# RGF_1_0.net
KiCad netlist of a schematic drawn in EAGLE
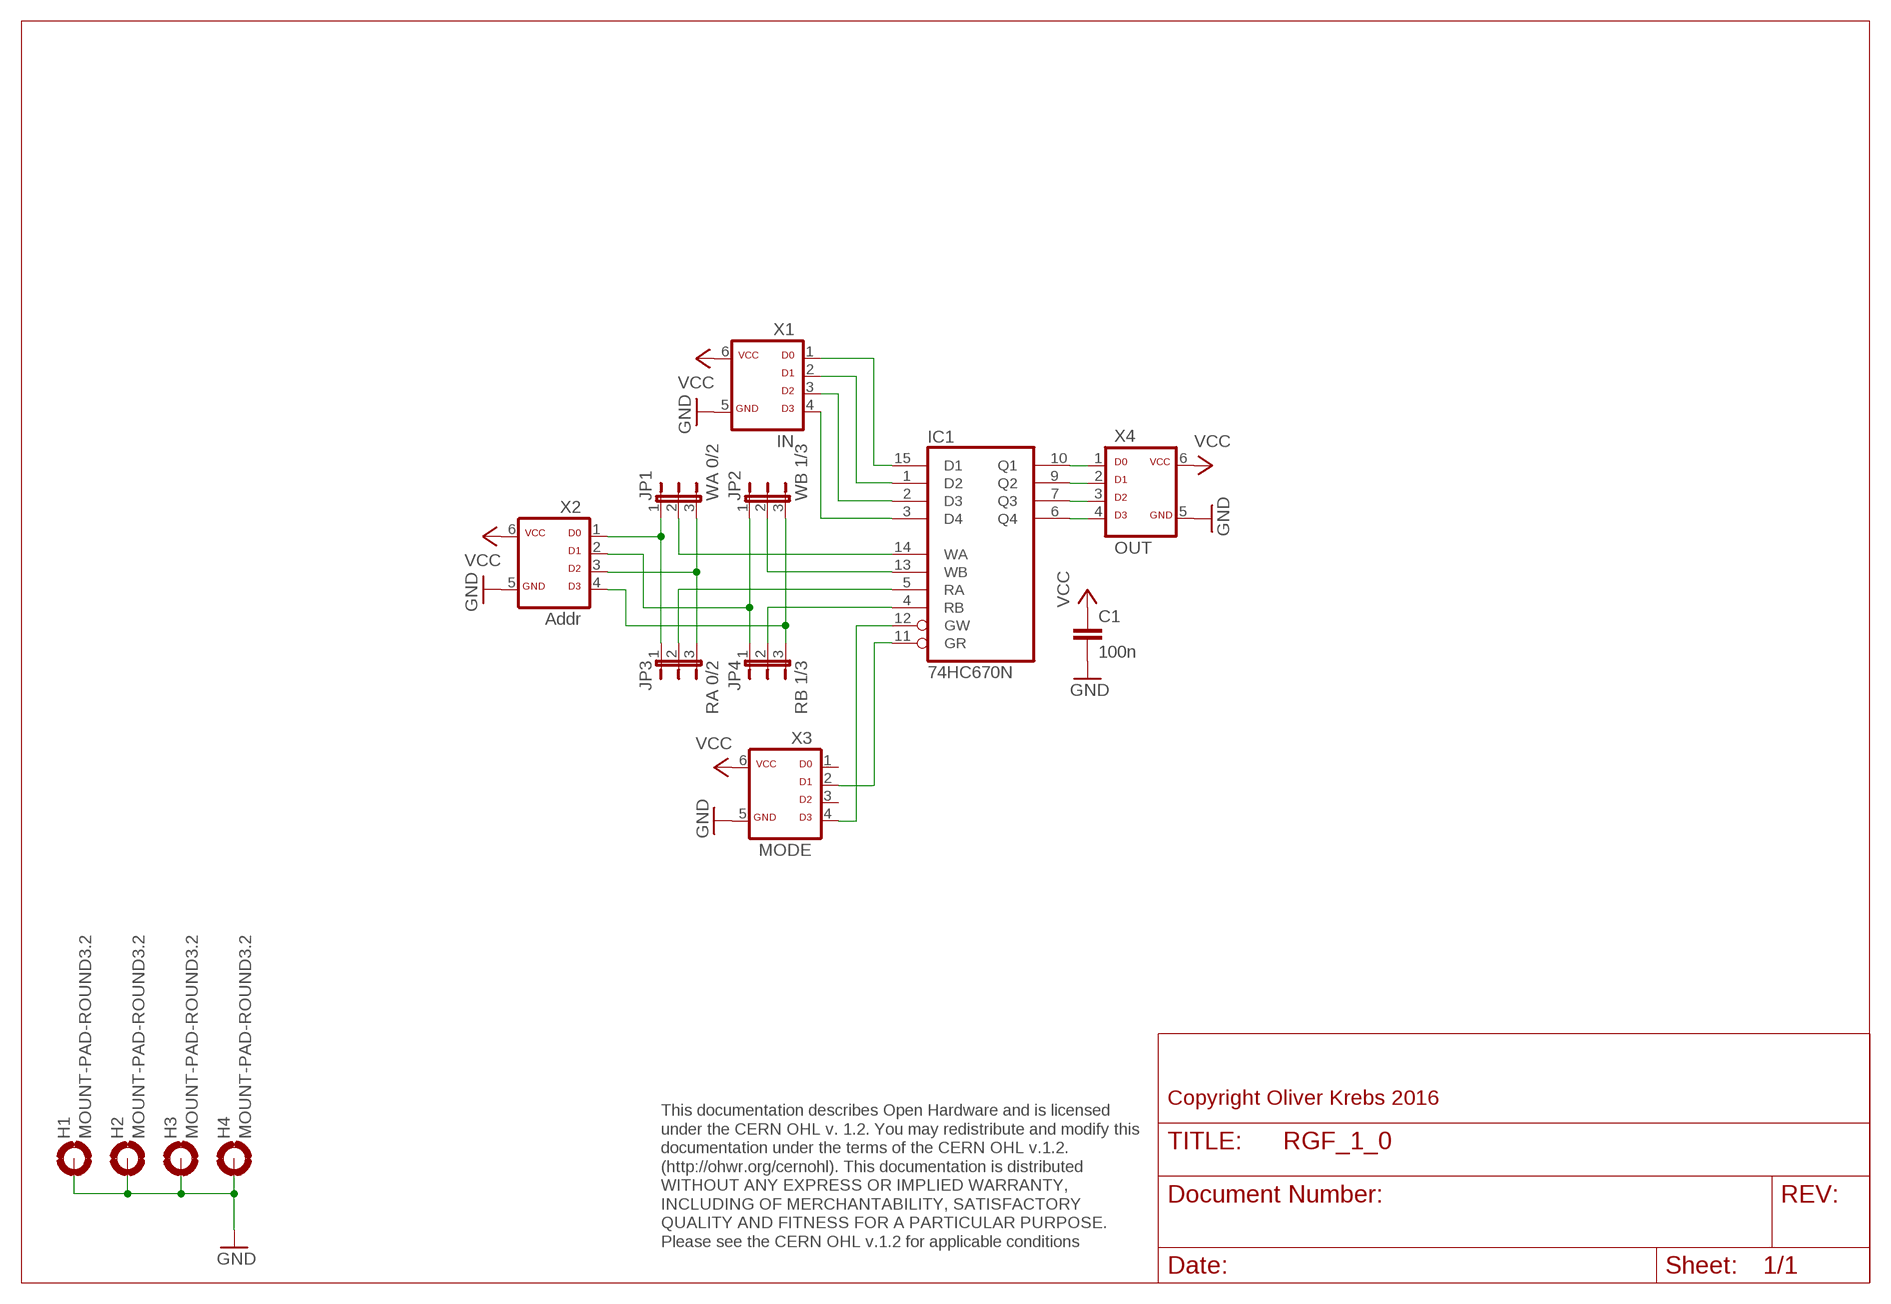
[diagram p0: schematic, sheet 1]

(export (version "E")
  (design (tool "Eeschema 10.0.6"))
  (components
    (comp (ref "C1")
      (value "100n")
      (footprint "eagle-import:C050-025X075")
      (libsource (lib "eagle-import") (part "C-EU050-025X075"))
    )
    (comp (ref "H1")
      (value "MOUNT-PAD-ROUND3.2")
      (footprint "eagle-import:3,2-PAD")
      (libsource (lib "eagle-import") (part "MOUNT-PAD-ROUND3.2"))
    )
    (comp (ref "H2")
      (value "MOUNT-PAD-ROUND3.2")
      (footprint "eagle-import:3,2-PAD")
      (libsource (lib "eagle-import") (part "MOUNT-PAD-ROUND3.2"))
    )
    (comp (ref "H3")
      (value "MOUNT-PAD-ROUND3.2")
      (footprint "eagle-import:3,2-PAD")
      (libsource (lib "eagle-import") (part "MOUNT-PAD-ROUND3.2"))
    )
    (comp (ref "H4")
      (value "MOUNT-PAD-ROUND3.2")
      (footprint "eagle-import:3,2-PAD")
      (libsource (lib "eagle-import") (part "MOUNT-PAD-ROUND3.2"))
    )
    (comp (ref "IC1")
      (value "74HC670N")
      (footprint "eagle-import:DIL16")
      (libsource (lib "eagle-import") (part "74670NHC"))
    )
    (comp (ref "JP1")
      (value "WA 0/2")
      (footprint "eagle-import:JP2")
      (libsource (lib "eagle-import") (part "JP2E"))
    )
    (comp (ref "JP2")
      (value "WB 1/3")
      (footprint "eagle-import:JP2")
      (libsource (lib "eagle-import") (part "JP2E"))
    )
    (comp (ref "JP3")
      (value "RA 0/2")
      (footprint "eagle-import:JP2")
      (libsource (lib "eagle-import") (part "JP2E"))
    )
    (comp (ref "JP4")
      (value "RB 1/3")
      (footprint "eagle-import:JP2")
      (libsource (lib "eagle-import") (part "JP2E"))
    )
    (comp (ref "X1")
      (value "IN")
      (footprint "eagle-import:ML-6")
      (libsource (lib "eagle-import") (part "ML6D"))
    )
    (comp (ref "X2")
      (value "Addr")
      (footprint "eagle-import:ML-6")
      (libsource (lib "eagle-import") (part "ML6D"))
    )
    (comp (ref "X3")
      (value "MODE")
      (footprint "eagle-import:ML-6")
      (libsource (lib "eagle-import") (part "ML6D"))
    )
    (comp (ref "X4")
      (value "OUT")
      (footprint "eagle-import:ML-6")
      (libsource (lib "eagle-import") (part "ML6D"))
    )
  )
  (nets
    (net (code "1") (name "GND") (class "Default")
      (node (ref "C1") (pin "2") (pinfunction "2_2") (pintype "passive"))
      (node (ref "H1") (pin "B3,2") (pinfunction "MOUNT_B3,2") (pintype "passive"))
      (node (ref "H2") (pin "B3,2") (pinfunction "MOUNT_B3,2") (pintype "passive"))
      (node (ref "H3") (pin "B3,2") (pinfunction "MOUNT_B3,2") (pintype "passive"))
      (node (ref "H4") (pin "B3,2") (pinfunction "MOUNT_B3,2") (pintype "passive"))
      (node (ref "X1") (pin "5") (pinfunction "5_5") (pintype "passive"))
      (node (ref "X2") (pin "5") (pinfunction "5_5") (pintype "passive"))
      (node (ref "X3") (pin "5") (pinfunction "5_5") (pintype "passive"))
      (node (ref "X4") (pin "5") (pinfunction "5_5") (pintype "passive"))
    )
    (net (code "2") (name "Net-(IC1A-D1)") (class "Default")
      (node (ref "IC1") (pin "15") (pinfunction "D1_15") (pintype "input"))
      (node (ref "X1") (pin "1") (pinfunction "1_1") (pintype "passive"))
    )
    (net (code "3") (name "Net-(IC1A-D2)") (class "Default")
      (node (ref "IC1") (pin "1") (pinfunction "D2_1") (pintype "input"))
      (node (ref "X1") (pin "2") (pinfunction "2_2") (pintype "passive"))
    )
    (net (code "4") (name "Net-(IC1A-D3)") (class "Default")
      (node (ref "IC1") (pin "2") (pinfunction "D3_2") (pintype "input"))
      (node (ref "X1") (pin "3") (pinfunction "3_3") (pintype "passive"))
    )
    (net (code "5") (name "Net-(IC1A-D4)") (class "Default")
      (node (ref "IC1") (pin "3") (pinfunction "D4_3") (pintype "input"))
      (node (ref "X1") (pin "4") (pinfunction "4_4") (pintype "passive"))
    )
    (net (code "6") (name "Net-(IC1A-GR)") (class "Default")
      (node (ref "IC1") (pin "11") (pinfunction "GR_11") (pintype "input"))
      (node (ref "X3") (pin "2") (pinfunction "2_2") (pintype "passive"))
    )
    (net (code "7") (name "Net-(IC1A-GW)") (class "Default")
      (node (ref "IC1") (pin "12") (pinfunction "GW_12") (pintype "input"))
      (node (ref "X3") (pin "4") (pinfunction "4_4") (pintype "passive"))
    )
    (net (code "8") (name "Net-(IC1A-Q1)") (class "Default")
      (node (ref "IC1") (pin "10") (pinfunction "Q1_10") (pintype "tri_state"))
      (node (ref "X4") (pin "1") (pinfunction "1_1") (pintype "passive"))
    )
    (net (code "9") (name "Net-(IC1A-Q2)") (class "Default")
      (node (ref "IC1") (pin "9") (pinfunction "Q2_9") (pintype "tri_state"))
      (node (ref "X4") (pin "2") (pinfunction "2_2") (pintype "passive"))
    )
    (net (code "10") (name "Net-(IC1A-Q3)") (class "Default")
      (node (ref "IC1") (pin "7") (pinfunction "Q3_7") (pintype "tri_state"))
      (node (ref "X4") (pin "3") (pinfunction "3_3") (pintype "passive"))
    )
    (net (code "11") (name "Net-(IC1A-Q4)") (class "Default")
      (node (ref "IC1") (pin "6") (pinfunction "Q4_6") (pintype "tri_state"))
      (node (ref "X4") (pin "4") (pinfunction "4_4") (pintype "passive"))
    )
    (net (code "12") (name "Net-(IC1A-RA)") (class "Default")
      (node (ref "IC1") (pin "5") (pinfunction "RA_5") (pintype "input"))
      (node (ref "JP3") (pin "2") (pinfunction "2_2") (pintype "passive"))
    )
    (net (code "13") (name "Net-(IC1A-RB)") (class "Default")
      (node (ref "IC1") (pin "4") (pinfunction "RB_4") (pintype "input"))
      (node (ref "JP4") (pin "2") (pinfunction "2_2") (pintype "passive"))
    )
    (net (code "14") (name "Net-(IC1A-WA)") (class "Default")
      (node (ref "IC1") (pin "14") (pinfunction "WA_14") (pintype "input"))
      (node (ref "JP1") (pin "2") (pinfunction "2_2") (pintype "passive"))
    )
    (net (code "15") (name "Net-(IC1A-WB)") (class "Default")
      (node (ref "IC1") (pin "13") (pinfunction "WB_13") (pintype "input"))
      (node (ref "JP2") (pin "2") (pinfunction "2_2") (pintype "passive"))
    )
    (net (code "16") (name "Net-(JP1-Pad1)") (class "Default")
      (node (ref "JP1") (pin "1") (pinfunction "1_1") (pintype "passive"))
      (node (ref "JP3") (pin "1") (pinfunction "1_1") (pintype "passive"))
      (node (ref "X2") (pin "1") (pinfunction "1_1") (pintype "passive"))
    )
    (net (code "17") (name "Net-(JP1-Pad3)") (class "Default")
      (node (ref "JP1") (pin "3") (pinfunction "3_3") (pintype "passive"))
      (node (ref "JP3") (pin "3") (pinfunction "3_3") (pintype "passive"))
      (node (ref "X2") (pin "3") (pinfunction "3_3") (pintype "passive"))
    )
    (net (code "18") (name "Net-(JP2-Pad1)") (class "Default")
      (node (ref "JP2") (pin "1") (pinfunction "1_1") (pintype "passive"))
      (node (ref "JP4") (pin "1") (pinfunction "1_1") (pintype "passive"))
      (node (ref "X2") (pin "2") (pinfunction "2_2") (pintype "passive"))
    )
    (net (code "19") (name "Net-(JP2-Pad3)") (class "Default")
      (node (ref "JP2") (pin "3") (pinfunction "3_3") (pintype "passive"))
      (node (ref "JP4") (pin "3") (pinfunction "3_3") (pintype "passive"))
      (node (ref "X2") (pin "4") (pinfunction "4_4") (pintype "passive"))
    )
    (net (code "20") (name "VCC") (class "Default")
      (node (ref "C1") (pin "1") (pinfunction "1_1") (pintype "passive"))
      (node (ref "X1") (pin "6") (pinfunction "6_6") (pintype "passive"))
      (node (ref "X2") (pin "6") (pinfunction "6_6") (pintype "passive"))
      (node (ref "X3") (pin "6") (pinfunction "6_6") (pintype "passive"))
      (node (ref "X4") (pin "6") (pinfunction "6_6") (pintype "passive"))
    )
    (net (code "21") (name "unconnected-(X3-Pad1)") (class "Default")
      (node (ref "X3") (pin "1") (pinfunction "1_1") (pintype "passive"))
    )
    (net (code "22") (name "unconnected-(X3-Pad3)") (class "Default")
      (node (ref "X3") (pin "3") (pinfunction "3_3") (pintype "passive"))
    )
  )
)
